# Prosthetic_Circuit_Draft.net
KiCad netlist of a schematic drawn in EAGLE
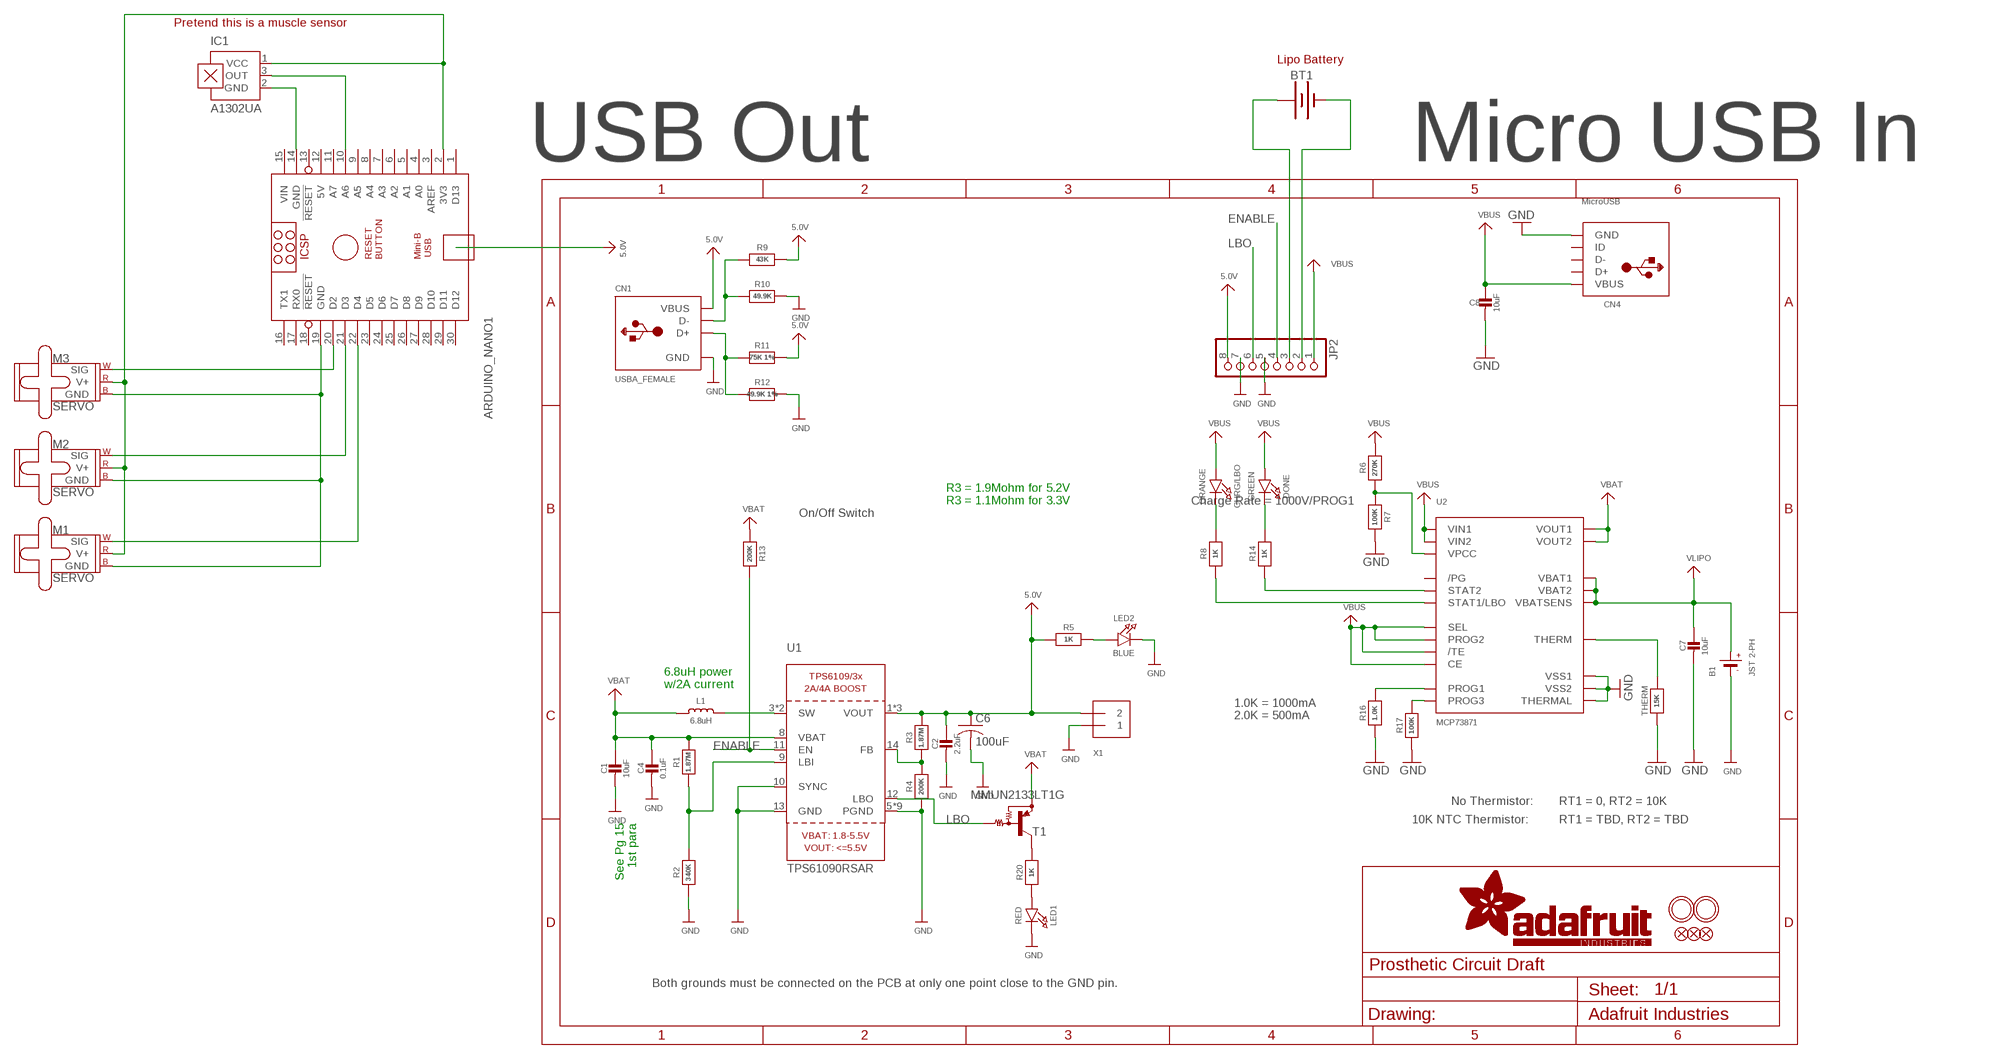
[diagram p0: schematic, sheet 1]

(export (version "E")
  (design (tool "Eeschema 10.0.6"))
  (components
    (comp (ref "ARDUINO_NANO1")
      (value "ARDUINO_NANO")
      (footprint "eagle-import:ARDUINO_NANO")
      (libsource (lib "eagle-import") (part "ARDUINO_NANO"))
    )
    (comp (ref "B1")
      (value "JST 2-PH")
      (footprint "eagle-import:JSTPH2")
      (libsource (lib "eagle-import") (part "BATTERY"))
    )
    (comp (ref "BT1")
      (value "BATTERY-9V")
      (footprint "eagle-import:BATTCON_9V")
      (libsource (lib "eagle-import") (part "BATTERY-9V"))
    )
    (comp (ref "C1")
      (value "10uF")
      (footprint "eagle-import:0805-NO")
      (libsource (lib "eagle-import") (part "CAP_CERAMIC0805-NOOUTLINE"))
    )
    (comp (ref "C2")
      (value "2.2uF")
      (footprint "eagle-import:0805-NO")
      (libsource (lib "eagle-import") (part "CAP_CERAMIC0805-NOOUTLINE"))
    )
    (comp (ref "C4")
      (value "0.1uF")
      (footprint "eagle-import:0805_10MGAP")
      (libsource (lib "eagle-import") (part "CAP_CERAMIC0805_10MGAP"))
    )
    (comp (ref "C6")
      (value "100uF")
      (footprint "eagle-import:C1210")
      (libsource (lib "eagle-import") (part "C-USC1210"))
    )
    (comp (ref "C7")
      (value "10uF")
      (footprint "eagle-import:0805-NO")
      (libsource (lib "eagle-import") (part "CAP_CERAMIC0805-NOOUTLINE"))
    )
    (comp (ref "C8")
      (value "10uF")
      (footprint "eagle-import:0805-NO")
      (libsource (lib "eagle-import") (part "CAP_CERAMIC0805-NOOUTLINE"))
    )
    (comp (ref "CHRG/LBO")
      (value "ORANGE")
      (footprint "eagle-import:CHIPLED_0805_NOOUTLINE")
      (libsource (lib "eagle-import") (part "LED0805_NOOUTLINE"))
    )
    (comp (ref "CN1")
      (value "USBA_FEMALE")
      (footprint "eagle-import:USB_HOST-PTH")
      (libsource (lib "eagle-import") (part "USB_TYPEAPTHFML"))
    )
    (comp (ref "CN4")
      (value "MicroUSB")
      (footprint "eagle-import:4UCONN_20329")
      (libsource (lib "eagle-import") (part "USBMICRO_20329"))
    )
    (comp (ref "DONE")
      (value "GREEN")
      (footprint "eagle-import:CHIPLED_0805_NOOUTLINE")
      (libsource (lib "eagle-import") (part "LED0805_NOOUTLINE"))
    )
    (comp (ref "FID1")
      (value "FIDUCIAL\"\"")
      (footprint "eagle-import:FIDUCIAL_1MM")
      (fields (field (name "BOM") "EXCLUDE"))
      (libsource (lib "eagle-import") (part "FIDUCIAL{dblquote}{dblquote}"))
    )
    (comp (ref "FID2")
      (value "FIDUCIAL\"\"")
      (footprint "eagle-import:FIDUCIAL_1MM")
      (libsource (lib "eagle-import") (part "FIDUCIAL{dblquote}{dblquote}"))
    )
    (comp (ref "FID3")
      (value "FIDUCIAL\"\"")
      (footprint "eagle-import:FIDUCIAL_1MM")
      (fields (field (name "BOM") "EXCLUDE"))
      (libsource (lib "eagle-import") (part "FIDUCIAL{dblquote}{dblquote}"))
    )
    (comp (ref "IC1")
      (value "A1302UA")
      (footprint "eagle-import:SIP3-UA")
      (fields (field (name "MF") "ALLEGRO MICROSYSTEMS, INC.") (field (name "MPN") "A1302EUA-T"))
      (libsource (lib "eagle-import") (part "A13?UA02"))
    )
    (comp (ref "JP2")
      (value "HEADER-1X8ROUND")
      (footprint "eagle-import:1X08_ROUND")
      (libsource (lib "eagle-import") (part "HEADER-1X8ROUND"))
    )
    (comp (ref "L1")
      (value "6.8uH")
      (footprint "eagle-import:INDUCTOR_5X5MM_TDK_VLC5045")
      (libsource (lib "eagle-import") (part "INDUCTORTDK_VLC5045"))
    )
    (comp (ref "LED1")
      (value "RED")
      (footprint "eagle-import:CHIPLED_0805_NOOUTLINE")
      (libsource (lib "eagle-import") (part "LED0805_NOOUTLINE"))
    )
    (comp (ref "LED2")
      (value "BLUE")
      (footprint "eagle-import:CHIPLED_0805_NOOUTLINE")
      (libsource (lib "eagle-import") (part "LED0805_NOOUTLINE"))
    )
    (comp (ref "M1")
      (value "SERVO")
      (footprint "eagle-import:1X03")
      (libsource (lib "eagle-import") (part "SERVO"))
    )
    (comp (ref "M2")
      (value "SERVO")
      (footprint "eagle-import:1X03")
      (libsource (lib "eagle-import") (part "SERVO"))
    )
    (comp (ref "M3")
      (value "SERVO")
      (footprint "eagle-import:1X03")
      (libsource (lib "eagle-import") (part "SERVO"))
    )
    (comp (ref "R1")
      (value "1.87M")
      (footprint "eagle-import:_0805MP")
      (libsource (lib "eagle-import") (part "RESISTOR_0805MP"))
    )
    (comp (ref "R2")
      (value "340K")
      (footprint "eagle-import:_0805MP")
      (libsource (lib "eagle-import") (part "RESISTOR_0805MP"))
    )
    (comp (ref "R3")
      (value "1.87M")
      (footprint "eagle-import:0805-NO")
      (libsource (lib "eagle-import") (part "RESISTOR0805_NOOUTLINE"))
    )
    (comp (ref "R4")
      (value "200K")
      (footprint "eagle-import:0805-NO")
      (libsource (lib "eagle-import") (part "RESISTOR0805_NOOUTLINE"))
    )
    (comp (ref "R5")
      (value "1K")
      (footprint "eagle-import:0805-NO")
      (libsource (lib "eagle-import") (part "RESISTOR0805_NOOUTLINE"))
    )
    (comp (ref "R6")
      (value "270K")
      (footprint "eagle-import:0805-NO")
      (libsource (lib "eagle-import") (part "RESISTOR0805_NOOUTLINE"))
    )
    (comp (ref "R7")
      (value "100K")
      (footprint "eagle-import:0805-NO")
      (libsource (lib "eagle-import") (part "RESISTOR0805_NOOUTLINE"))
    )
    (comp (ref "R8")
      (value "1K")
      (footprint "eagle-import:0805-NO")
      (libsource (lib "eagle-import") (part "RESISTOR0805_NOOUTLINE"))
    )
    (comp (ref "R9")
      (value "43K")
      (footprint "eagle-import:0805-NO")
      (libsource (lib "eagle-import") (part "RESISTOR0805_NOOUTLINE"))
    )
    (comp (ref "R10")
      (value "49.9K")
      (footprint "eagle-import:0805-NO")
      (libsource (lib "eagle-import") (part "RESISTOR0805_NOOUTLINE"))
    )
    (comp (ref "R11")
      (value "75K 1%")
      (footprint "eagle-import:0805-NO")
      (libsource (lib "eagle-import") (part "RESISTOR0805_NOOUTLINE"))
    )
    (comp (ref "R12")
      (value "49.9K 1%")
      (footprint "eagle-import:0805-NO")
      (libsource (lib "eagle-import") (part "RESISTOR0805_NOOUTLINE"))
    )
    (comp (ref "R13")
      (value "200K")
      (footprint "eagle-import:0805-NO")
      (libsource (lib "eagle-import") (part "RESISTOR0805_NOOUTLINE"))
    )
    (comp (ref "R14")
      (value "1K")
      (footprint "eagle-import:0805-NO")
      (libsource (lib "eagle-import") (part "RESISTOR0805_NOOUTLINE"))
    )
    (comp (ref "R16")
      (value "1.0K")
      (footprint "eagle-import:0805-NO")
      (libsource (lib "eagle-import") (part "RESISTOR0805_NOOUTLINE"))
    )
    (comp (ref "R17")
      (value "100K")
      (footprint "eagle-import:0805-NO")
      (libsource (lib "eagle-import") (part "RESISTOR0805_NOOUTLINE"))
    )
    (comp (ref "R20")
      (value "1K")
      (footprint "eagle-import:0805-NO")
      (libsource (lib "eagle-import") (part "RESISTOR0805_NOOUTLINE"))
    )
    (comp (ref "T1")
      (value "MMUN2133LT1G")
      (footprint "eagle-import:SC59-BEC")
      (libsource (lib "eagle-import") (part "-PNP_DRIVER-SC59-BECMUN2114T1"))
    )
    (comp (ref "THERM")
      (value "15K")
      (footprint "eagle-import:0805-NO")
      (libsource (lib "eagle-import") (part "RESISTOR0805_NOOUTLINE"))
    )
    (comp (ref "U$10")
      (value "MOUNTINGHOLE2.5")
      (footprint "eagle-import:MOUNTINGHOLE_2.5_PLATED")
      (libsource (lib "eagle-import") (part "MOUNTINGHOLE2.5"))
    )
    (comp (ref "U$11")
      (value "MOUNTINGHOLE2.5")
      (footprint "eagle-import:MOUNTINGHOLE_2.5_PLATED")
      (libsource (lib "eagle-import") (part "MOUNTINGHOLE2.5"))
    )
    (comp (ref "U1")
      (value "TPS61090RSAR")
      (footprint "eagle-import:PVQFN-16")
      (libsource (lib "eagle-import") (part "VREG_TPS6103X"))
    )
    (comp (ref "U2")
      (value "MCP73871")
      (footprint "eagle-import:QFN20_4MM")
      (libsource (lib "eagle-import") (part "MCP73871"))
    )
    (comp (ref "X1")
      (value "TERMBLOCK_1X2")
      (footprint "eagle-import:TERMBLOCK_1X2-3.5MM")
      (libsource (lib "eagle-import") (part "TERMBLOCK_1X2"))
    )
  )
  (nets
    (net (code "1") (name "/5V") (class "Default")
      (node (ref "ARDUINO_NANO1") (pin "12") (pinfunction "5V_12") (pintype "power_in"))
    )
    (net (code "2") (name "/ENABLE") (class "Default")
      (node (ref "JP2") (pin "4") (pinfunction "4_4") (pintype "passive"))
      (node (ref "R13") (pin "2") (pinfunction "2_2") (pintype "passive"))
      (node (ref "U1") (pin "11") (pinfunction "EN_11") (pintype "input"))
    )
    (net (code "3") (name "/LBO") (class "Default")
      (node (ref "JP2") (pin "6") (pinfunction "6_6") (pintype "passive"))
      (node (ref "T1") (pin "B") (pinfunction "B_B") (pintype "passive"))
      (node (ref "U1") (pin "12") (pinfunction "LBO_12") (pintype "output"))
    )
    (net (code "4") (name "/VIN") (class "Default")
      (node (ref "ARDUINO_NANO1") (pin "15") (pinfunction "VIN_15") (pintype "power_in"))
    )
    (net (code "5") (name "5.0V") (class "Default")
      (node (ref "C2") (pin "1") (pinfunction "1_1") (pintype "passive"))
      (node (ref "C6") (pin "1") (pinfunction "1_1") (pintype "passive"))
      (node (ref "CN1") (pin "VBUS") (pinfunction "VBUS_VBUS") (pintype "power_in"))
      (node (ref "JP2") (pin "8") (pinfunction "8_8") (pintype "passive"))
      (node (ref "R11") (pin "2") (pinfunction "2_2") (pintype "passive"))
      (node (ref "R3") (pin "2") (pinfunction "2_2") (pintype "passive"))
      (node (ref "R5") (pin "1") (pinfunction "1_1") (pintype "passive"))
      (node (ref "R9") (pin "2") (pinfunction "2_2") (pintype "passive"))
      (node (ref "U1") (pin "1") (pinfunction "VOUT_1") (pintype "power_in"))
      (node (ref "U1") (pin "15") (pinfunction "VOUT_15") (pintype "power_in"))
      (node (ref "U1") (pin "16") (pinfunction "VOUT_16") (pintype "power_in"))
      (node (ref "X1") (pin "2") (pinfunction "2_2") (pintype "passive"))
    )
    (net (code "6") (name "GND") (class "Default")
      (node (ref "B1") (pin "1") (pinfunction "-_1") (pintype "passive"))
      (node (ref "C1") (pin "2") (pinfunction "2_2") (pintype "passive"))
      (node (ref "C2") (pin "2") (pinfunction "2_2") (pintype "passive"))
      (node (ref "C4") (pin "2") (pinfunction "2_2") (pintype "passive"))
      (node (ref "C6") (pin "2") (pinfunction "2_2") (pintype "passive"))
      (node (ref "C7") (pin "2") (pinfunction "2_2") (pintype "passive"))
      (node (ref "C8") (pin "2") (pinfunction "2_2") (pintype "passive"))
      (node (ref "CN1") (pin "GND") (pinfunction "GND_GND") (pintype "power_in"))
      (node (ref "CN4") (pin "BASE@1") (pinfunction "GND_BASE@1") (pintype "power_in"))
      (node (ref "CN4") (pin "BASE@2") (pinfunction "GND_BASE@2") (pintype "power_in"))
      (node (ref "CN4") (pin "GND") (pinfunction "GND_GND") (pintype "power_in"))
      (node (ref "CN4") (pin "SPRT@1") (pinfunction "GND_SPRT@1") (pintype "power_in"))
      (node (ref "CN4") (pin "SPRT@2") (pinfunction "GND_SPRT@2") (pintype "power_in"))
      (node (ref "CN4") (pin "SPRT@3") (pinfunction "GND_SPRT@3") (pintype "power_in"))
      (node (ref "CN4") (pin "SPRT@4") (pinfunction "GND_SPRT@4") (pintype "power_in"))
      (node (ref "JP2") (pin "5") (pinfunction "5_5") (pintype "passive"))
      (node (ref "JP2") (pin "7") (pinfunction "7_7") (pintype "passive"))
      (node (ref "LED1") (pin "C") (pinfunction "C_C") (pintype "passive"))
      (node (ref "LED2") (pin "C") (pinfunction "C_C") (pintype "passive"))
      (node (ref "R10") (pin "2") (pinfunction "2_2") (pintype "passive"))
      (node (ref "R12") (pin "2") (pinfunction "2_2") (pintype "passive"))
      (node (ref "R16") (pin "1") (pinfunction "1_1") (pintype "passive"))
      (node (ref "R17") (pin "1") (pinfunction "1_1") (pintype "passive"))
      (node (ref "R2") (pin "1") (pinfunction "1_1") (pintype "passive"))
      (node (ref "R4") (pin "1") (pinfunction "1_1") (pintype "passive"))
      (node (ref "R7") (pin "2") (pinfunction "2_2") (pintype "passive"))
      (node (ref "THERM") (pin "1") (pinfunction "1_1") (pintype "passive"))
      (node (ref "U1") (pin "10") (pinfunction "SYNC_10") (pintype "input"))
      (node (ref "U1") (pin "13") (pinfunction "GND_13") (pintype "power_in"))
      (node (ref "U1") (pin "5") (pinfunction "PGND_5") (pintype "power_in"))
      (node (ref "U1") (pin "6") (pinfunction "PGND_6") (pintype "power_in"))
      (node (ref "U1") (pin "7") (pinfunction "PGND_7") (pintype "power_in"))
      (node (ref "U1") (pin "P$18") (pinfunction "PGND_P$18") (pintype "power_in"))
      (node (ref "U1") (pin "P$19") (pinfunction "PGND_P$19") (pintype "power_in"))
      (node (ref "U1") (pin "P$20") (pinfunction "PGND_P$20") (pintype "power_in"))
      (node (ref "U1") (pin "P$21") (pinfunction "PGND_P$21") (pintype "power_in"))
      (node (ref "U1") (pin "P$22") (pinfunction "PGND_P$22") (pintype "power_in"))
      (node (ref "U1") (pin "THERMAL") (pinfunction "PGND_THERMAL") (pintype "power_in"))
      (node (ref "U2") (pin "P$10") (pinfunction "VSS1_P$10") (pintype "bidirectional"))
      (node (ref "U2") (pin "P$11") (pinfunction "VSS2_P$11") (pintype "bidirectional"))
      (node (ref "U2") (pin "P$21") (pinfunction "THERMAL_P$21") (pintype "bidirectional"))
      (node (ref "X1") (pin "1") (pinfunction "1_1") (pintype "passive"))
    )
    (net (code "7") (name "Net-(ARDUINO_NANO1-3V3)") (class "Default")
      (node (ref "ARDUINO_NANO1") (pin "2") (pinfunction "3V3_2") (pintype "output"))
      (node (ref "IC1") (pin "1") (pinfunction "VCC_1") (pintype "power_in"))
      (node (ref "M1") (pin "2") (pinfunction "V+_2") (pintype "bidirectional"))
      (node (ref "M2") (pin "2") (pinfunction "V+_2") (pintype "bidirectional"))
      (node (ref "M3") (pin "2") (pinfunction "V+_2") (pintype "bidirectional"))
    )
    (net (code "8") (name "Net-(ARDUINO_NANO1-A6)") (class "Default")
      (node (ref "ARDUINO_NANO1") (pin "10") (pinfunction "A6_10") (pintype "bidirectional"))
      (node (ref "IC1") (pin "3") (pinfunction "OUT_3") (pintype "output"))
    )
    (net (code "9") (name "Net-(ARDUINO_NANO1-D2)") (class "Default")
      (node (ref "ARDUINO_NANO1") (pin "20") (pinfunction "D2_20") (pintype "bidirectional"))
      (node (ref "M3") (pin "1") (pinfunction "SIG_1") (pintype "bidirectional"))
    )
    (net (code "10") (name "Net-(ARDUINO_NANO1-D3)") (class "Default")
      (node (ref "ARDUINO_NANO1") (pin "21") (pinfunction "D3_21") (pintype "bidirectional"))
      (node (ref "M2") (pin "1") (pinfunction "SIG_1") (pintype "bidirectional"))
    )
    (net (code "11") (name "Net-(ARDUINO_NANO1-D4)") (class "Default")
      (node (ref "ARDUINO_NANO1") (pin "22") (pinfunction "D4_22") (pintype "bidirectional"))
      (node (ref "M1") (pin "1") (pinfunction "SIG_1") (pintype "bidirectional"))
    )
    (net (code "12") (name "Net-(BT1-Pad+)") (class "Default")
      (node (ref "BT1") (pin "+") (pinfunction "+_+") (pintype "power_in"))
      (node (ref "JP2") (pin "3") (pinfunction "3_3") (pintype "passive"))
    )
    (net (code "13") (name "Net-(BT1-Pad-)") (class "Default")
      (node (ref "BT1") (pin "-") (pinfunction "-_-") (pintype "power_in"))
      (node (ref "JP2") (pin "2") (pinfunction "2_2") (pintype "passive"))
    )
    (net (code "14") (name "Net-(CHRG/LBO-PadC)") (class "Default")
      (node (ref "CHRG/LBO") (pin "C") (pinfunction "C_C") (pintype "passive"))
      (node (ref "R8") (pin "2") (pinfunction "2_2") (pintype "passive"))
    )
    (net (code "15") (name "Net-(CN1-PadD+)") (class "Default")
      (node (ref "CN1") (pin "D+") (pinfunction "D+_D+") (pintype "bidirectional"))
      (node (ref "R11") (pin "1") (pinfunction "1_1") (pintype "passive"))
      (node (ref "R12") (pin "1") (pinfunction "1_1") (pintype "passive"))
    )
    (net (code "16") (name "Net-(CN1-PadD-)") (class "Default")
      (node (ref "CN1") (pin "D-") (pinfunction "D-_D-") (pintype "bidirectional"))
      (node (ref "R10") (pin "1") (pinfunction "1_1") (pintype "passive"))
      (node (ref "R9") (pin "1") (pinfunction "1_1") (pintype "passive"))
    )
    (net (code "17") (name "Net-(DONE-PadC)") (class "Default")
      (node (ref "DONE") (pin "C") (pinfunction "C_C") (pintype "passive"))
      (node (ref "R14") (pin "2") (pinfunction "2_2") (pintype "passive"))
    )
    (net (code "18") (name "Net-(IC1-GND)") (class "Default")
      (node (ref "ARDUINO_NANO1") (pin "14") (pinfunction "GND_14") (pintype "power_in"))
      (node (ref "IC1") (pin "2") (pinfunction "GND_2") (pintype "power_in"))
    )
    (net (code "19") (name "Net-(L1-2)") (class "Default")
      (node (ref "L1") (pin "P$2") (pinfunction "2_P$2") (pintype "passive"))
      (node (ref "U1") (pin "3") (pinfunction "SW_3") (pintype "input"))
      (node (ref "U1") (pin "4") (pinfunction "SW_4") (pintype "input"))
    )
    (net (code "20") (name "Net-(LED1-PadA)") (class "Default")
      (node (ref "LED1") (pin "A") (pinfunction "A_A") (pintype "passive"))
      (node (ref "R20") (pin "1") (pinfunction "1_1") (pintype "passive"))
    )
    (net (code "21") (name "Net-(LED2-PadA)") (class "Default")
      (node (ref "LED2") (pin "A") (pinfunction "A_A") (pintype "passive"))
      (node (ref "R5") (pin "2") (pinfunction "2_2") (pintype "passive"))
    )
    (net (code "22") (name "Net-(M1-GND)") (class "Default")
      (node (ref "ARDUINO_NANO1") (pin "19") (pinfunction "GND_19") (pintype "power_in"))
      (node (ref "M1") (pin "3") (pinfunction "GND_3") (pintype "bidirectional"))
      (node (ref "M2") (pin "3") (pinfunction "GND_3") (pintype "bidirectional"))
      (node (ref "M3") (pin "3") (pinfunction "GND_3") (pintype "bidirectional"))
    )
    (net (code "23") (name "Net-(R20-Pad2)") (class "Default")
      (node (ref "R20") (pin "2") (pinfunction "2_2") (pintype "passive"))
      (node (ref "T1") (pin "C") (pinfunction "C_C") (pintype "passive"))
    )
    (net (code "24") (name "Net-(U1-FB)") (class "Default")
      (node (ref "R3") (pin "1") (pinfunction "1_1") (pintype "passive"))
      (node (ref "R4") (pin "2") (pinfunction "2_2") (pintype "passive"))
      (node (ref "U1") (pin "14") (pinfunction "FB_14") (pintype "input"))
    )
    (net (code "25") (name "Net-(U1-LBI)") (class "Default")
      (node (ref "R1") (pin "1") (pinfunction "1_1") (pintype "passive"))
      (node (ref "R2") (pin "2") (pinfunction "2_2") (pintype "passive"))
      (node (ref "U1") (pin "9") (pinfunction "LBI_9") (pintype "input"))
    )
    (net (code "26") (name "Net-(U2-PROG1)") (class "Default")
      (node (ref "R16") (pin "2") (pinfunction "2_2") (pintype "passive"))
      (node (ref "U2") (pin "P$13") (pinfunction "PROG1_P$13") (pintype "bidirectional"))
    )
    (net (code "27") (name "Net-(U2-PROG3)") (class "Default")
      (node (ref "R17") (pin "2") (pinfunction "2_2") (pintype "passive"))
      (node (ref "U2") (pin "P$12") (pinfunction "PROG3_P$12") (pintype "bidirectional"))
    )
    (net (code "28") (name "Net-(U2-STAT1{slash}LBO)") (class "Default")
      (node (ref "R8") (pin "1") (pinfunction "1_1") (pintype "passive"))
      (node (ref "U2") (pin "P$8") (pinfunction "STAT1/LBO_P$8") (pintype "bidirectional"))
    )
    (net (code "29") (name "Net-(U2-STAT2)") (class "Default")
      (node (ref "R14") (pin "1") (pinfunction "1_1") (pintype "passive"))
      (node (ref "U2") (pin "P$7") (pinfunction "STAT2_P$7") (pintype "bidirectional"))
    )
    (net (code "30") (name "Net-(U2-THERM)") (class "Default")
      (node (ref "THERM") (pin "2") (pinfunction "2_2") (pintype "passive"))
      (node (ref "U2") (pin "P$5") (pinfunction "THERM_P$5") (pintype "bidirectional"))
    )
    (net (code "31") (name "Net-(U2-VPCC)") (class "Default")
      (node (ref "R6") (pin "1") (pinfunction "1_1") (pintype "passive"))
      (node (ref "R7") (pin "1") (pinfunction "1_1") (pintype "passive"))
      (node (ref "U2") (pin "P$2") (pinfunction "VPCC_P$2") (pintype "bidirectional"))
    )
    (net (code "32") (name "VBAT") (class "Default")
      (node (ref "C1") (pin "1") (pinfunction "1_1") (pintype "passive"))
      (node (ref "C4") (pin "1") (pinfunction "1_1") (pintype "passive"))
      (node (ref "L1") (pin "P$1") (pinfunction "1_P$1") (pintype "passive"))
      (node (ref "R1") (pin "2") (pinfunction "2_2") (pintype "passive"))
      (node (ref "R13") (pin "1") (pinfunction "1_1") (pintype "passive"))
      (node (ref "T1") (pin "E") (pinfunction "E_E") (pintype "passive"))
      (node (ref "U1") (pin "8") (pinfunction "VBAT_8") (pintype "input"))
      (node (ref "U2") (pin "P$1") (pinfunction "VOUT1_P$1") (pintype "bidirectional"))
      (node (ref "U2") (pin "P$20") (pinfunction "VOUT2_P$20") (pintype "bidirectional"))
    )
    (net (code "33") (name "VBUS") (class "Default")
      (node (ref "C8") (pin "1") (pinfunction "1_1") (pintype "passive"))
      (node (ref "CHRG/LBO") (pin "A") (pinfunction "A_A") (pintype "passive"))
      (node (ref "CN4") (pin "VBUS") (pinfunction "VBUS_VBUS") (pintype "power_in"))
      (node (ref "DONE") (pin "A") (pinfunction "A_A") (pintype "passive"))
      (node (ref "JP2") (pin "1") (pinfunction "1_1") (pintype "passive"))
      (node (ref "R6") (pin "2") (pinfunction "2_2") (pintype "passive"))
      (node (ref "U2") (pin "P$17") (pinfunction "CE_P$17") (pintype "bidirectional"))
      (node (ref "U2") (pin "P$18") (pinfunction "VIN1_P$18") (pintype "bidirectional"))
      (node (ref "U2") (pin "P$19") (pinfunction "VIN2_P$19") (pintype "bidirectional"))
      (node (ref "U2") (pin "P$3") (pinfunction "SEL_P$3") (pintype "bidirectional"))
      (node (ref "U2") (pin "P$4") (pinfunction "PROG2_P$4") (pintype "bidirectional"))
      (node (ref "U2") (pin "P$9") (pinfunction "/TE_P$9") (pintype "bidirectional"))
    )
    (net (code "34") (name "VLIPO") (class "Default")
      (node (ref "B1") (pin "2") (pinfunction "+_2") (pintype "passive"))
      (node (ref "C7") (pin "1") (pinfunction "1_1") (pintype "passive"))
      (node (ref "U2") (pin "P$14") (pinfunction "VBAT1_P$14") (pintype "bidirectional"))
      (node (ref "U2") (pin "P$15") (pinfunction "VBAT2_P$15") (pintype "bidirectional"))
      (node (ref "U2") (pin "P$16") (pinfunction "VBATSENS_P$16") (pintype "bidirectional"))
    )
    (net (code "35") (name "unconnected-(ARDUINO_NANO1-A0-Pad4)") (class "Default")
      (node (ref "ARDUINO_NANO1") (pin "4") (pinfunction "A0_4") (pintype "bidirectional"))
    )
    (net (code "36") (name "unconnected-(ARDUINO_NANO1-A1-Pad5)") (class "Default")
      (node (ref "ARDUINO_NANO1") (pin "5") (pinfunction "A1_5") (pintype "bidirectional"))
    )
    (net (code "37") (name "unconnected-(ARDUINO_NANO1-A2-Pad6)") (class "Default")
      (node (ref "ARDUINO_NANO1") (pin "6") (pinfunction "A2_6") (pintype "bidirectional"))
    )
    (net (code "38") (name "unconnected-(ARDUINO_NANO1-A3-Pad7)") (class "Default")
      (node (ref "ARDUINO_NANO1") (pin "7") (pinfunction "A3_7") (pintype "bidirectional"))
    )
    (net (code "39") (name "unconnected-(ARDUINO_NANO1-A4-Pad8)") (class "Default")
      (node (ref "ARDUINO_NANO1") (pin "8") (pinfunction "A4_8") (pintype "bidirectional"))
    )
    (net (code "40") (name "unconnected-(ARDUINO_NANO1-A5-Pad9)") (class "Default")
      (node (ref "ARDUINO_NANO1") (pin "9") (pinfunction "A5_9") (pintype "bidirectional"))
    )
    (net (code "41") (name "unconnected-(ARDUINO_NANO1-A7-Pad11)") (class "Default")
      (node (ref "ARDUINO_NANO1") (pin "11") (pinfunction "A7_11") (pintype "bidirectional"))
    )
    (net (code "42") (name "unconnected-(ARDUINO_NANO1-AREF-Pad3)") (class "Default")
      (node (ref "ARDUINO_NANO1") (pin "3") (pinfunction "AREF_3") (pintype "input"))
    )
    (net (code "43") (name "unconnected-(ARDUINO_NANO1-D5-Pad23)") (class "Default")
      (node (ref "ARDUINO_NANO1") (pin "23") (pinfunction "D5_23") (pintype "bidirectional"))
    )
    (net (code "44") (name "unconnected-(ARDUINO_NANO1-D6-Pad24)") (class "Default")
      (node (ref "ARDUINO_NANO1") (pin "24") (pinfunction "D6_24") (pintype "bidirectional"))
    )
    (net (code "45") (name "unconnected-(ARDUINO_NANO1-D7-Pad25)") (class "Default")
      (node (ref "ARDUINO_NANO1") (pin "25") (pinfunction "D7_25") (pintype "bidirectional"))
    )
    (net (code "46") (name "unconnected-(ARDUINO_NANO1-D8-Pad26)") (class "Default")
      (node (ref "ARDUINO_NANO1") (pin "26") (pinfunction "D8_26") (pintype "bidirectional"))
    )
    (net (code "47") (name "unconnected-(ARDUINO_NANO1-D9-Pad27)") (class "Default")
      (node (ref "ARDUINO_NANO1") (pin "27") (pinfunction "D9_27") (pintype "bidirectional"))
    )
    (net (code "48") (name "unconnected-(ARDUINO_NANO1-D10-Pad28)") (class "Default")
      (node (ref "ARDUINO_NANO1") (pin "28") (pinfunction "D10_28") (pintype "bidirectional"))
    )
    (net (code "49") (name "unconnected-(ARDUINO_NANO1-D11-Pad29)") (class "Default")
      (node (ref "ARDUINO_NANO1") (pin "29") (pinfunction "D11_29") (pintype "bidirectional"))
    )
    (net (code "50") (name "unconnected-(ARDUINO_NANO1-D12-Pad30)") (class "Default")
      (node (ref "ARDUINO_NANO1") (pin "30") (pinfunction "D12_30") (pintype "bidirectional"))
    )
    (net (code "51") (name "unconnected-(ARDUINO_NANO1-D13-Pad1)") (class "Default")
      (node (ref "ARDUINO_NANO1") (pin "1") (pinfunction "D13_1") (pintype "bidirectional"))
    )
    (net (code "52") (name "unconnected-(ARDUINO_NANO1-RX0-Pad17)") (class "Default")
      (node (ref "ARDUINO_NANO1") (pin "17") (pinfunction "RX0_17") (pintype "bidirectional"))
    )
    (net (code "53") (name "unconnected-(ARDUINO_NANO1-TX1-Pad16)") (class "Default")
      (node (ref "ARDUINO_NANO1") (pin "16") (pinfunction "TX1_16") (pintype "bidirectional"))
    )
    (net (code "54") (name "unconnected-(ARDUINO_NANO1-~{RESET}-Pad13)") (class "Default")
      (node (ref "ARDUINO_NANO1") (pin "13") (pinfunction "~{RESET}_13") (pintype "input"))
    )
    (net (code "55") (name "unconnected-(ARDUINO_NANO1-~{RESET}-Pad18)") (class "Default")
      (node (ref "ARDUINO_NANO1") (pin "18") (pinfunction "~{RESET}_18") (pintype "input"))
    )
    (net (code "56") (name "unconnected-(CN4-PadD+)") (class "Default")
      (node (ref "CN4") (pin "D+") (pinfunction "D+_D+") (pintype "bidirectional"))
    )
    (net (code "57") (name "unconnected-(CN4-PadD-)") (class "Default")
      (node (ref "CN4") (pin "D-") (pinfunction "D-_D-") (pintype "bidirectional"))
    )
    (net (code "58") (name "unconnected-(CN4-PadID)") (class "Default")
      (node (ref "CN4") (pin "ID") (pinfunction "ID_ID") (pintype "bidirectional"))
    )
    (net (code "59") (name "unconnected-(U2-{slash}PG-PadP$6)") (class "Default")
      (node (ref "U2") (pin "P$6") (pinfunction "/PG_P$6") (pintype "bidirectional"))
    )
  )
)
